# RTL8201F.net
KiCad netlist of a schematic drawn in Altium Designer
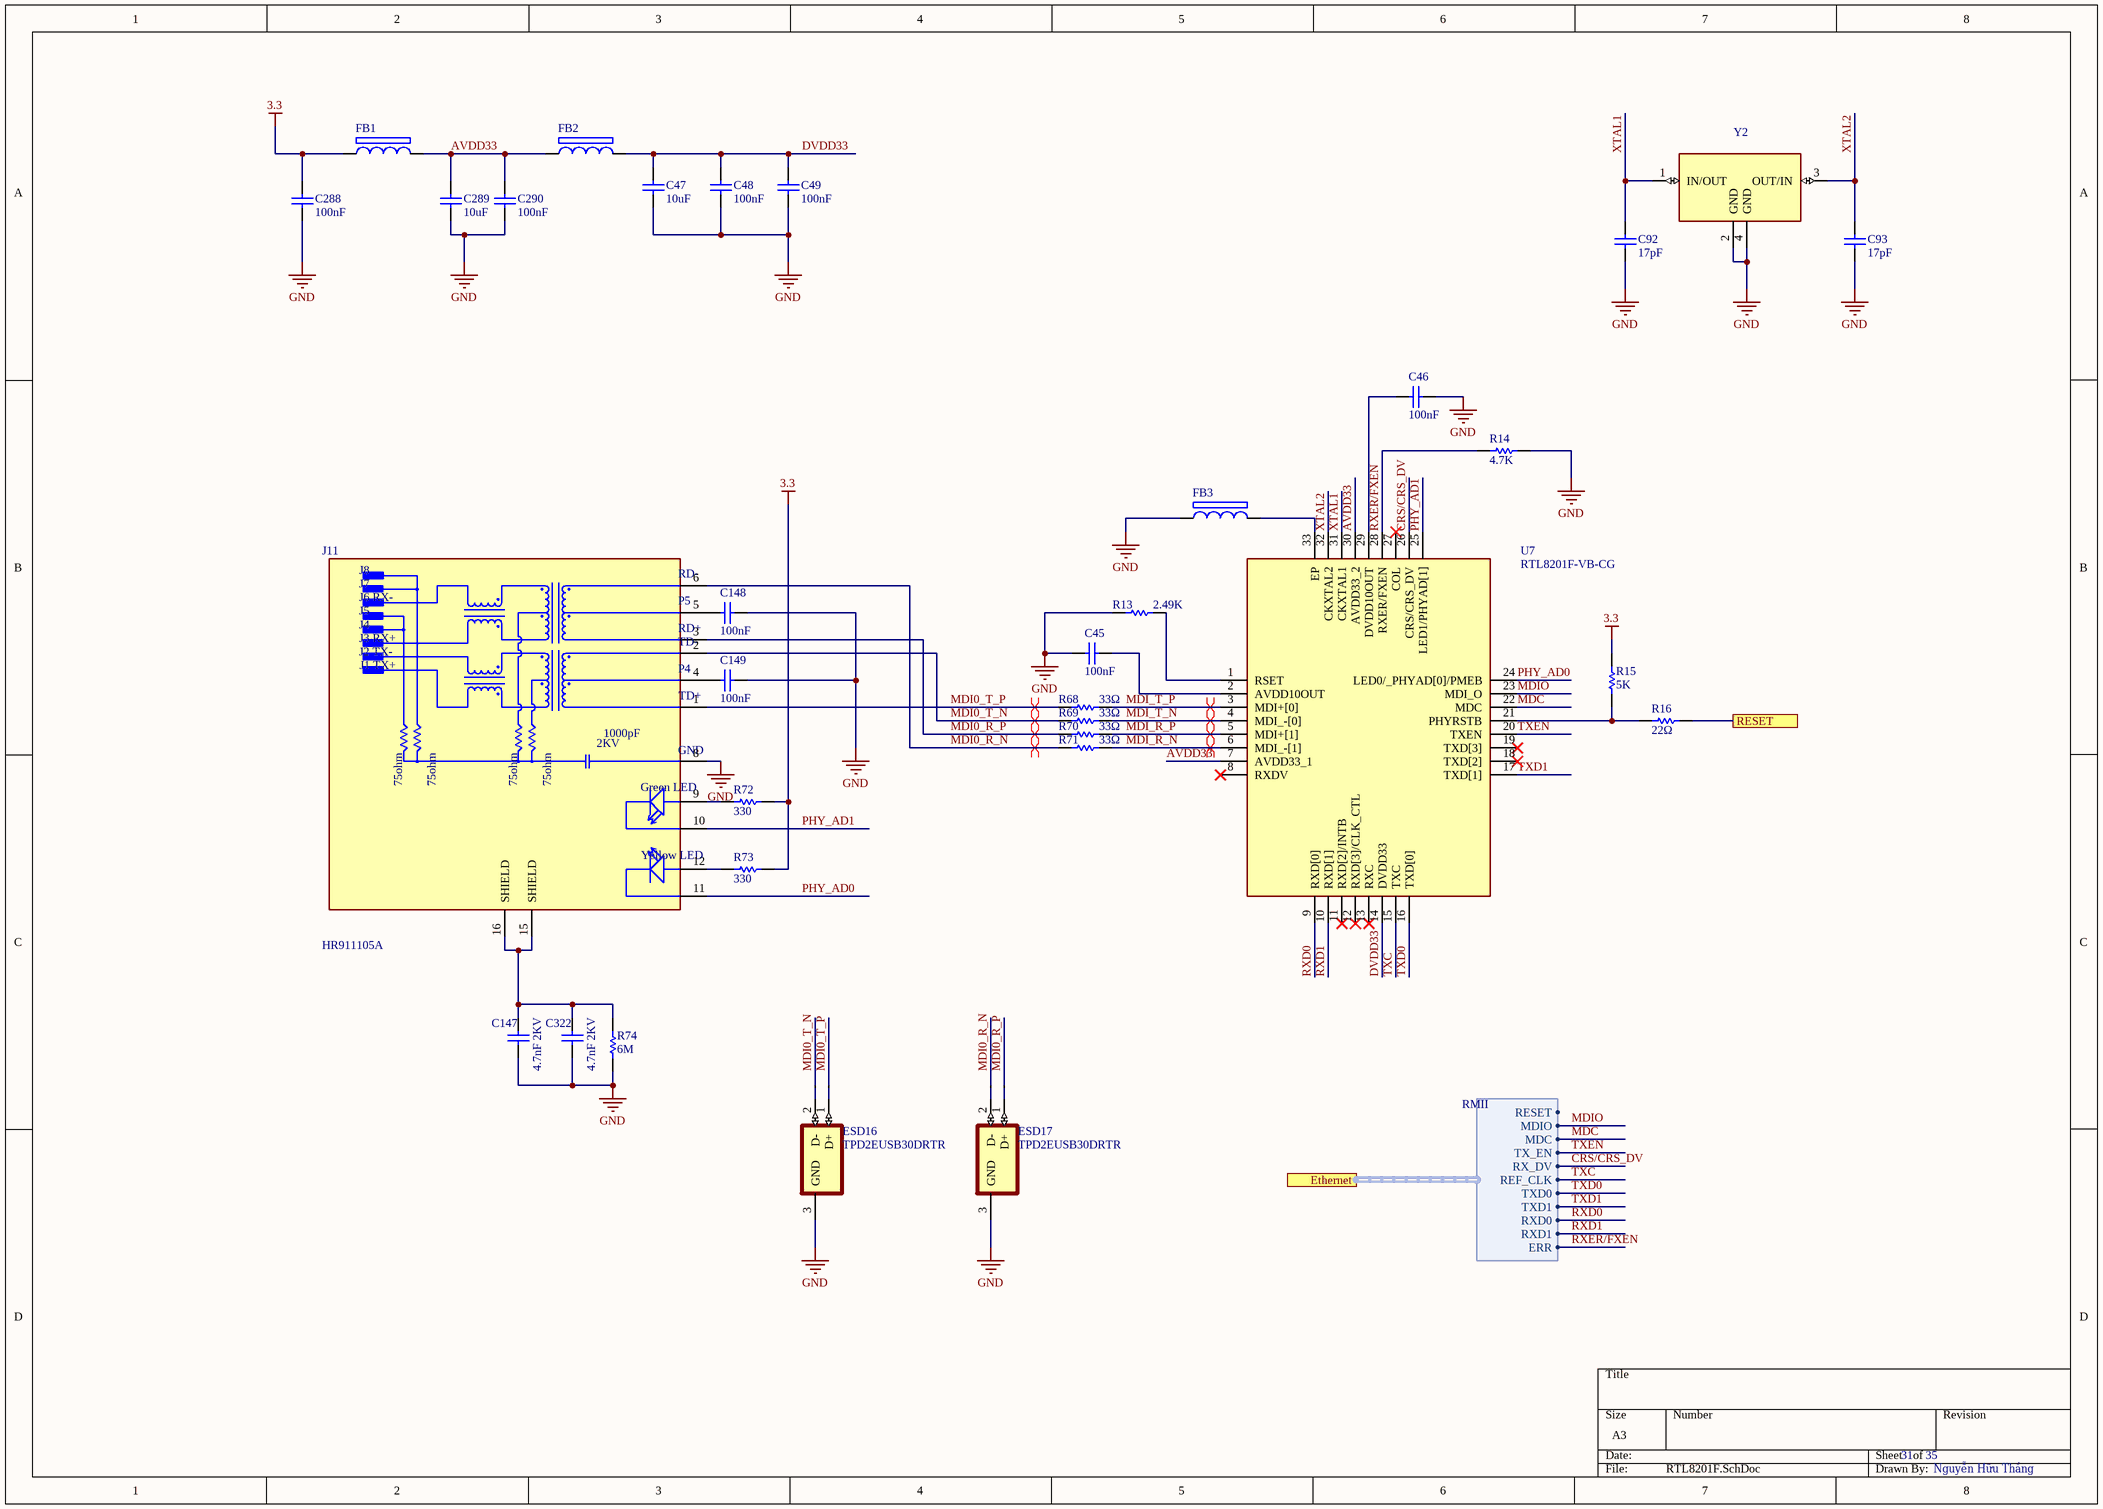
[diagram p0: RTL8201F.SchDoc]

(export (version "E")
  (design (tool "Eeschema 10.0.6"))
  (components
    (comp (ref ".10") (value "P") (footprint "P") (libsource (lib "kit") (part "P")))
    (comp (ref ".12") (value "P") (footprint "P") (libsource (lib "kit") (part "P")))
    (comp (ref ".15") (value "P") (footprint "P") (libsource (lib "kit") (part "P")))
    (comp (ref ".16") (value "P") (footprint "P") (libsource (lib "kit") (part "P")))
    (comp (ref "C45")
      (value "100nF")
      (footprint "C0603")
      (fields (field (name "Comment") "C0603"))
      (libsource (lib "kit") (part "C0603"))
    )
    (comp (ref "C46")
      (value "100nF")
      (footprint "C0603")
      (fields (field (name "Comment") "C0603"))
      (libsource (lib "kit") (part "C0603"))
    )
    (comp (ref "C47")
      (value "10uF")
      (footprint "C1210")
      (fields (field (name "Comment") "C1210"))
      (libsource (lib "kit") (part "C1210"))
    )
    (comp (ref "C48")
      (value "100nF")
      (footprint "C0603")
      (fields (field (name "Comment") "C0603"))
      (libsource (lib "kit") (part "C0603"))
    )
    (comp (ref "C49")
      (value "100nF")
      (footprint "C0603")
      (fields (field (name "Comment") "C0603"))
      (libsource (lib "kit") (part "C0603"))
    )
    (comp (ref "C92")
      (value "17pF")
      (footprint "C0402")
      (description "nên chọn tụ từ 14 đến 20 với LGE25.000M")
      (fields (field (name "Comment") "C0402"))
      (libsource (lib "kit") (part "C0402"))
    )
    (comp (ref "C93")
      (value "17pF")
      (footprint "C0402")
      (description "nên chọn tụ từ 14 đến 20 với LGE25.000M")
      (fields (field (name "Comment") "C0402"))
      (libsource (lib "kit") (part "C0402"))
    )
    (comp (ref "C147")
      (value "4.7nF 2KV")
      (footprint "C1210")
      (fields (field (name "Comment") "C1210"))
      (libsource (lib "kit") (part "C1210"))
    )
    (comp (ref "C148")
      (value "100nF")
      (footprint "C0603")
      (fields (field (name "Comment") "C0603"))
      (libsource (lib "kit") (part "C0603"))
    )
    (comp (ref "C149")
      (value "100nF")
      (footprint "C0603")
      (fields (field (name "Comment") "C0603"))
      (libsource (lib "kit") (part "C0603"))
    )
    (comp (ref "C288")
      (value "100nF")
      (footprint "C0603")
      (fields (field (name "Comment") "C0603"))
      (libsource (lib "kit") (part "C0603"))
    )
    (comp (ref "C289")
      (value "10uF")
      (footprint "C1210")
      (fields (field (name "Comment") "C1210"))
      (libsource (lib "kit") (part "C1210"))
    )
    (comp (ref "C290")
      (value "100nF")
      (footprint "C0603")
      (fields (field (name "Comment") "C0603"))
      (libsource (lib "kit") (part "C0603"))
    )
    (comp (ref "C322")
      (value "4.7nF 2KV")
      (footprint "C1210")
      (fields (field (name "Comment") "C1210"))
      (libsource (lib "kit") (part "C1210"))
    )
    (comp (ref "ESD16")
      (value "TPD2EUSB30DRTR")
      (footprint "SOTFL35P100X50-3N")
      (description "2-channel ESD solution for SuperSpeed USB 3.0 interface 3-SOT-9X3 -40 to 85")
      (libsource (lib "kit") (part "TPD2EUSB30DRTR"))
    )
    (comp (ref "ESD17")
      (value "TPD2EUSB30DRTR")
      (footprint "SOTFL35P100X50-3N")
      (description "2-channel ESD solution for SuperSpeed USB 3.0 interface 3-SOT-9X3 -40 to 85")
      (libsource (lib "kit") (part "TPD2EUSB30DRTR"))
    )
    (comp (ref "FB1")
      (value "BLM18KG121TN1D")
      (footprint "BLM18EG101TH1D")
      (description "Ferrite Bead. 0603. 3A.  DC Resistance(DCR) 30mΩ. 120Ω@100MHz")
      (fields (field (name "MOUSER PART NUMBER") "81-BLM18KG121TN1D"))
      (libsource (lib "kit") (part "BLM18KG121TN1D"))
    )
    (comp (ref "FB2")
      (value "BLM18KG121TN1D")
      (footprint "BLM18EG101TH1D")
      (description "Ferrite Bead. 0603. 3A.  DC Resistance(DCR) 30mΩ. 120Ω@100MHz")
      (fields (field (name "MOUSER PART NUMBER") "81-BLM18KG121TN1D"))
      (libsource (lib "kit") (part "BLM18KG121TN1D"))
    )
    (comp (ref "FB3")
      (value "BLM18KG121TN1D")
      (footprint "BLM18EG101TH1D")
      (description "Ferrite Bead. 0603. 3A.  DC Resistance(DCR) 30mΩ. 120Ω@100MHz")
      (fields (field (name "MOUSER PART NUMBER") "81-BLM18KG121TN1D"))
      (libsource (lib "kit") (part "BLM18KG121TN1D"))
    )
    (comp (ref "J11")
      (value "HR911105A")
      (footprint "HANRUN_HR911105A")
      (description "RJ45 có biến áp")
      (libsource (lib "kit") (part "HR911105A"))
    )
    (comp (ref "R13")
      (value "2.49K")
      (footprint "R0603")
      (fields (field (name "Comment") "R0603"))
      (libsource (lib "kit") (part "R0603"))
    )
    (comp (ref "R14")
      (value "4.7K")
      (footprint "R0603")
      (fields (field (name "Comment") "R0603"))
      (libsource (lib "kit") (part "R0603"))
    )
    (comp (ref "R15")
      (value "5K")
      (footprint "R0603")
      (fields (field (name "Comment") "R0603"))
      (libsource (lib "kit") (part "R0603"))
    )
    (comp (ref "R16")
      (value "22Ω")
      (footprint "R0603")
      (fields (field (name "Comment") "R0603"))
      (libsource (lib "kit") (part "R0603"))
    )
    (comp (ref "R68")
      (value "33Ω")
      (footprint "R0603")
      (fields (field (name "Comment") "R0603"))
      (libsource (lib "kit") (part "R0603"))
    )
    (comp (ref "R69")
      (value "33Ω")
      (footprint "R0603")
      (fields (field (name "Comment") "R0603"))
      (libsource (lib "kit") (part "R0603"))
    )
    (comp (ref "R70")
      (value "33Ω")
      (footprint "R0603")
      (fields (field (name "Comment") "R0603"))
      (libsource (lib "kit") (part "R0603"))
    )
    (comp (ref "R71")
      (value "33Ω")
      (footprint "R0603")
      (fields (field (name "Comment") "R0603"))
      (libsource (lib "kit") (part "R0603"))
    )
    (comp (ref "R72")
      (value "330")
      (footprint "R0603")
      (fields (field (name "Comment") "R0603"))
      (libsource (lib "kit") (part "R0603"))
    )
    (comp (ref "R73")
      (value "330")
      (footprint "R0603")
      (fields (field (name "Comment") "R0603"))
      (libsource (lib "kit") (part "R0603"))
    )
    (comp (ref "R74")
      (value "6M")
      (footprint "R0603")
      (fields (field (name "Comment") "R0603"))
      (libsource (lib "kit") (part "R0603"))
    )
    (comp (ref "U7")
      (value "RTL8201F-VB-CG")
      (footprint "RTL8201F")
      (description "Integrated Circuit")
      (libsource (lib "kit") (part "RTL8201F-VB-CG"))
    )
    (comp (ref "Y2")
      (value "LGE25.000M")
      (footprint "XTAL_ECS-250-6-33B2-CTN-TR3")
      (description "Crystals 25.0000MHZ 12pF SMD 30Ω")
      (libsource (lib "kit") (part "LGE25.000M"))
    )
  )
  (nets
    (net (code "2") (name "/AVDD33") (class "Default")
      (node (ref "C289") (pin "2") (pinfunction "2_2") (pintype "passive"))
      (node (ref "C290") (pin "2") (pinfunction "2_2") (pintype "passive"))
      (node (ref "FB1") (pin "2") (pinfunction "2_2") (pintype "passive"))
      (node (ref "FB2") (pin "1") (pinfunction "1_1") (pintype "passive"))
      (node (ref "U7") (pin "30") (pinfunction "AVDD33_2_30") (pintype "passive"))
      (node (ref "U7") (pin "7") (pinfunction "AVDD33_1_7") (pintype "passive"))
    )
    (net (code "3") (name "/CRS{slash}CRS_DV") (class "Default")
      (node (ref "U7") (pin "26") (pinfunction "CRS/CRS_DV_26") (pintype "passive"))
    )
    (net (code "4") (name "/DVDD33") (class "Default")
      (node (ref "C47") (pin "2") (pinfunction "2_2") (pintype "passive"))
      (node (ref "C48") (pin "2") (pinfunction "2_2") (pintype "passive"))
      (node (ref "C49") (pin "2") (pinfunction "2_2") (pintype "passive"))
      (node (ref "FB2") (pin "2") (pinfunction "2_2") (pintype "passive"))
      (node (ref "U7") (pin "14") (pinfunction "DVDD33_14") (pintype "passive"))
    )
    (net (code "5") (name "/MDC") (class "Default")
      (node (ref "U7") (pin "22") (pinfunction "MDC_22") (pintype "passive"))
    )
    (net (code "6") (name "/MDI0_R_N") (class "Default")
      (node (ref ".15") (pin "2") (pinfunction "2_2") (pintype "passive"))
      (node (ref "J11") (pin "6") (pinfunction "RD-_6") (pintype "passive"))
      (node (ref "R71") (pin "1") (pinfunction "1_1") (pintype "passive"))
    )
    (net (code "7") (name "/MDI0_R_P") (class "Default")
      (node (ref ".16") (pin "2") (pinfunction "2_2") (pintype "passive"))
      (node (ref "J11") (pin "3") (pinfunction "RD+_3") (pintype "passive"))
      (node (ref "R70") (pin "1") (pinfunction "1_1") (pintype "passive"))
    )
    (net (code "8") (name "/MDI0_T_N") (class "Default")
      (node (ref ".10") (pin "2") (pinfunction "2_2") (pintype "passive"))
      (node (ref "J11") (pin "2") (pinfunction "TD-_2") (pintype "passive"))
      (node (ref "R69") (pin "1") (pinfunction "1_1") (pintype "passive"))
    )
    (net (code "9") (name "/MDI0_T_P") (class "Default")
      (node (ref ".12") (pin "2") (pinfunction "2_2") (pintype "passive"))
      (node (ref "J11") (pin "1") (pinfunction "TD+_1") (pintype "passive"))
      (node (ref "R68") (pin "1") (pinfunction "1_1") (pintype "passive"))
    )
    (net (code "10") (name "/MDIO") (class "Default")
      (node (ref "U7") (pin "23") (pinfunction "MDI_O_23") (pintype "passive"))
    )
    (net (code "11") (name "/MDI_R_N") (class "Default")
      (node (ref "R71") (pin "2") (pinfunction "2_2") (pintype "passive"))
      (node (ref "U7") (pin "6") (pinfunction "MDI_-[1]_6") (pintype "passive"))
    )
    (net (code "12") (name "/MDI_R_P") (class "Default")
      (node (ref "R70") (pin "2") (pinfunction "2_2") (pintype "passive"))
      (node (ref "U7") (pin "5") (pinfunction "MDI+[1]_5") (pintype "passive"))
    )
    (net (code "13") (name "/MDI_T_N") (class "Default")
      (node (ref "R69") (pin "2") (pinfunction "2_2") (pintype "passive"))
      (node (ref "U7") (pin "4") (pinfunction "MDI_-[0]_4") (pintype "passive"))
    )
    (net (code "14") (name "/MDI_T_P") (class "Default")
      (node (ref "R68") (pin "2") (pinfunction "2_2") (pintype "passive"))
      (node (ref "U7") (pin "3") (pinfunction "MDI+[0]_3") (pintype "passive"))
    )
    (net (code "15") (name "/PHY_AD0") (class "Default")
      (node (ref "J11") (pin "11") (pinfunction "YC_11") (pintype "passive"))
      (node (ref "U7") (pin "24") (pinfunction "LED0/_PHYAD[0]/PMEB_24") (pintype "passive"))
    )
    (net (code "16") (name "/PHY_AD1") (class "Default")
      (node (ref "J11") (pin "10") (pinfunction "GC_10") (pintype "passive"))
      (node (ref "U7") (pin "25") (pinfunction "LED1/PHYAD[1]_25") (pintype "passive"))
    )
    (net (code "17") (name "/RESET") (class "Default")
      (node (ref "R16") (pin "2") (pinfunction "2_2") (pintype "passive"))
    )
    (net (code "18") (name "/RXD0") (class "Default")
      (node (ref "U7") (pin "9") (pinfunction "RXD[0]_9") (pintype "passive"))
    )
    (net (code "19") (name "/RXD1") (class "Default")
      (node (ref "U7") (pin "10") (pinfunction "RXD[1]_10") (pintype "passive"))
    )
    (net (code "20") (name "/RXER{slash}FXEN") (class "Default")
      (node (ref "R14") (pin "1") (pinfunction "1_1") (pintype "passive"))
      (node (ref "U7") (pin "28") (pinfunction "RXER/FXEN_28") (pintype "passive"))
    )
    (net (code "21") (name "/TXC") (class "Default")
      (node (ref "U7") (pin "15") (pinfunction "TXC_15") (pintype "passive"))
    )
    (net (code "22") (name "/TXD0") (class "Default")
      (node (ref "U7") (pin "16") (pinfunction "TXD[0]_16") (pintype "passive"))
    )
    (net (code "23") (name "/TXD1") (class "Default")
      (node (ref "U7") (pin "17") (pinfunction "TXD[1]_17") (pintype "passive"))
    )
    (net (code "24") (name "/TXEN") (class "Default")
      (node (ref "U7") (pin "20") (pinfunction "TXEN_20") (pintype "passive"))
    )
    (net (code "25") (name "/XTAL1") (class "Default")
      (node (ref "C92") (pin "2") (pinfunction "2_2") (pintype "passive"))
      (node (ref "U7") (pin "31") (pinfunction "CKXTAL1_31") (pintype "passive"))
      (node (ref "Y2") (pin "1") (pinfunction "IN/OUT_1") (pintype "bidirectional"))
    )
    (net (code "26") (name "/XTAL2") (class "Default")
      (node (ref "C93") (pin "2") (pinfunction "2_2") (pintype "passive"))
      (node (ref "U7") (pin "32") (pinfunction "CKXTAL2_32") (pintype "passive"))
      (node (ref "Y2") (pin "3") (pinfunction "OUT/IN_3") (pintype "bidirectional"))
    )
    (net (code "28") (name "3.3") (class "Default")
      (node (ref "C288") (pin "2") (pinfunction "2_2") (pintype "passive"))
      (node (ref "FB1") (pin "1") (pinfunction "1_1") (pintype "passive"))
      (node (ref "R15") (pin "2") (pinfunction "2_2") (pintype "passive"))
      (node (ref "R72") (pin "2") (pinfunction "2_2") (pintype "passive"))
      (node (ref "R73") (pin "2") (pinfunction "2_2") (pintype "passive"))
    )
    (net (code "29") (name "GND") (class "Default")
      (node (ref "C147") (pin "1") (pinfunction "1_1") (pintype "passive"))
      (node (ref "C148") (pin "1") (pinfunction "1_1") (pintype "passive"))
      (node (ref "C149") (pin "1") (pinfunction "1_1") (pintype "passive"))
      (node (ref "C288") (pin "1") (pinfunction "1_1") (pintype "passive"))
      (node (ref "C289") (pin "1") (pinfunction "1_1") (pintype "passive"))
      (node (ref "C290") (pin "1") (pinfunction "1_1") (pintype "passive"))
      (node (ref "C322") (pin "1") (pinfunction "1_1") (pintype "passive"))
      (node (ref "C45") (pin "2") (pinfunction "2_2") (pintype "passive"))
      (node (ref "C46") (pin "1") (pinfunction "1_1") (pintype "passive"))
      (node (ref "C47") (pin "1") (pinfunction "1_1") (pintype "passive"))
      (node (ref "C48") (pin "1") (pinfunction "1_1") (pintype "passive"))
      (node (ref "C49") (pin "1") (pinfunction "1_1") (pintype "passive"))
      (node (ref "C92") (pin "1") (pinfunction "1_1") (pintype "passive"))
      (node (ref "C93") (pin "1") (pinfunction "1_1") (pintype "passive"))
      (node (ref "ESD16") (pin "3") (pinfunction "GND_3") (pintype "power_in"))
      (node (ref "ESD17") (pin "3") (pinfunction "GND_3") (pintype "power_in"))
      (node (ref "FB3") (pin "1") (pinfunction "1_1") (pintype "passive"))
      (node (ref "J11") (pin "8") (pinfunction "GND_8") (pintype "power_in"))
      (node (ref "R13") (pin "1") (pinfunction "1_1") (pintype "passive"))
      (node (ref "R14") (pin "2") (pinfunction "2_2") (pintype "passive"))
      (node (ref "R74") (pin "2") (pinfunction "2_2") (pintype "passive"))
      (node (ref "Y2") (pin "2") (pinfunction "GND_2") (pintype "power_in"))
      (node (ref "Y2") (pin "4") (pinfunction "GND_4") (pintype "power_in"))
    )
    (net (code "30") (name "Net-(C147-Pad2)") (class "Default")
      (node (ref "C147") (pin "2") (pinfunction "2_2") (pintype "passive"))
      (node (ref "C322") (pin "2") (pinfunction "2_2") (pintype "passive"))
      (node (ref "J11") (pin "15") (pinfunction "SHIELD_15") (pintype "passive"))
      (node (ref "J11") (pin "16") (pinfunction "SHIELD_16") (pintype "passive"))
      (node (ref "R74") (pin "1") (pinfunction "1_1") (pintype "passive"))
    )
    (net (code "31") (name "Net-(ESD16-D+)") (class "Default")
      (node (ref ".12") (pin "1") (pinfunction "1_1") (pintype "passive"))
      (node (ref "ESD16") (pin "1") (pinfunction "D+_1") (pintype "bidirectional"))
    )
    (net (code "32") (name "Net-(ESD16-D-)") (class "Default")
      (node (ref ".10") (pin "1") (pinfunction "1_1") (pintype "passive"))
      (node (ref "ESD16") (pin "2") (pinfunction "D-_2") (pintype "bidirectional"))
    )
    (net (code "33") (name "Net-(ESD17-D+)") (class "Default")
      (node (ref ".16") (pin "1") (pinfunction "1_1") (pintype "passive"))
      (node (ref "ESD17") (pin "1") (pinfunction "D+_1") (pintype "bidirectional"))
    )
    (net (code "34") (name "Net-(ESD17-D-)") (class "Default")
      (node (ref ".15") (pin "1") (pinfunction "1_1") (pintype "passive"))
      (node (ref "ESD17") (pin "2") (pinfunction "D-_2") (pintype "bidirectional"))
    )
    (net (code "35") (name "Net-(J11-GA)") (class "Default")
      (node (ref "J11") (pin "9") (pinfunction "GA_9") (pintype "passive"))
      (node (ref "R72") (pin "1") (pinfunction "1_1") (pintype "passive"))
    )
    (net (code "36") (name "Net-(J11-P4)") (class "Default")
      (node (ref "C149") (pin "2") (pinfunction "2_2") (pintype "passive"))
      (node (ref "J11") (pin "4") (pinfunction "P4_4") (pintype "passive"))
    )
    (net (code "37") (name "Net-(J11-P5)") (class "Default")
      (node (ref "C148") (pin "2") (pinfunction "2_2") (pintype "passive"))
      (node (ref "J11") (pin "5") (pinfunction "P5_5") (pintype "passive"))
    )
    (net (code "38") (name "Net-(J11-YA)") (class "Default")
      (node (ref "J11") (pin "12") (pinfunction "YA_12") (pintype "passive"))
      (node (ref "R73") (pin "1") (pinfunction "1_1") (pintype "passive"))
    )
    (net (code "39") (name "Net-(U7-AVDD10OUT)") (class "Default")
      (node (ref "C45") (pin "1") (pinfunction "1_1") (pintype "passive"))
      (node (ref "U7") (pin "2") (pinfunction "AVDD10OUT_2") (pintype "passive"))
    )
    (net (code "40") (name "Net-(U7-DVDD10OUT)") (class "Default")
      (node (ref "C46") (pin "2") (pinfunction "2_2") (pintype "passive"))
      (node (ref "U7") (pin "29") (pinfunction "DVDD10OUT_29") (pintype "passive"))
    )
    (net (code "41") (name "Net-(U7-EP)") (class "Default")
      (node (ref "FB3") (pin "2") (pinfunction "2_2") (pintype "passive"))
      (node (ref "U7") (pin "33") (pinfunction "EP_33") (pintype "passive"))
    )
    (net (code "42") (name "Net-(U7-PHYRSTB)") (class "Default")
      (node (ref "R15") (pin "1") (pinfunction "1_1") (pintype "passive"))
      (node (ref "R16") (pin "1") (pinfunction "1_1") (pintype "passive"))
      (node (ref "U7") (pin "21") (pinfunction "PHYRSTB_21") (pintype "passive"))
    )
    (net (code "43") (name "Net-(U7-RSET)") (class "Default")
      (node (ref "R13") (pin "2") (pinfunction "2_2") (pintype "passive"))
      (node (ref "U7") (pin "1") (pinfunction "RSET_1") (pintype "passive"))
    )
    (net (code "44") (name "unconnected-(U7-COL-Pad27)") (class "Default")
      (node (ref "U7") (pin "27") (pinfunction "COL_27") (pintype "passive+no_connect"))
    )
    (net (code "45") (name "unconnected-(U7-RXC-Pad13)") (class "Default")
      (node (ref "U7") (pin "13") (pinfunction "RXC_13") (pintype "passive+no_connect"))
    )
    (net (code "46") (name "unconnected-(U7-RXDV-Pad8)") (class "Default")
      (node (ref "U7") (pin "8") (pinfunction "RXDV_8") (pintype "passive+no_connect"))
    )
    (net (code "47") (name "unconnected-(U7-RXD[2]{slash}INTB-Pad11)") (class "Default")
      (node (ref "U7") (pin "11") (pinfunction "RXD[2]/INTB_11") (pintype "passive+no_connect"))
    )
    (net (code "48") (name "unconnected-(U7-RXD[3]{slash}CLK_CTL-Pad12)") (class "Default")
      (node (ref "U7") (pin "12") (pinfunction "RXD[3]/CLK_CTL_12") (pintype "passive+no_connect"))
    )
    (net (code "49") (name "unconnected-(U7-TXD[2]-Pad18)") (class "Default")
      (node (ref "U7") (pin "18") (pinfunction "TXD[2]_18") (pintype "passive+no_connect"))
    )
    (net (code "50") (name "unconnected-(U7-TXD[3]-Pad19)") (class "Default")
      (node (ref "U7") (pin "19") (pinfunction "TXD[3]_19") (pintype "passive+no_connect"))
    )
  )
)
